# 3-9.net
KiCad netlist of a schematic drawn in Altium Designer
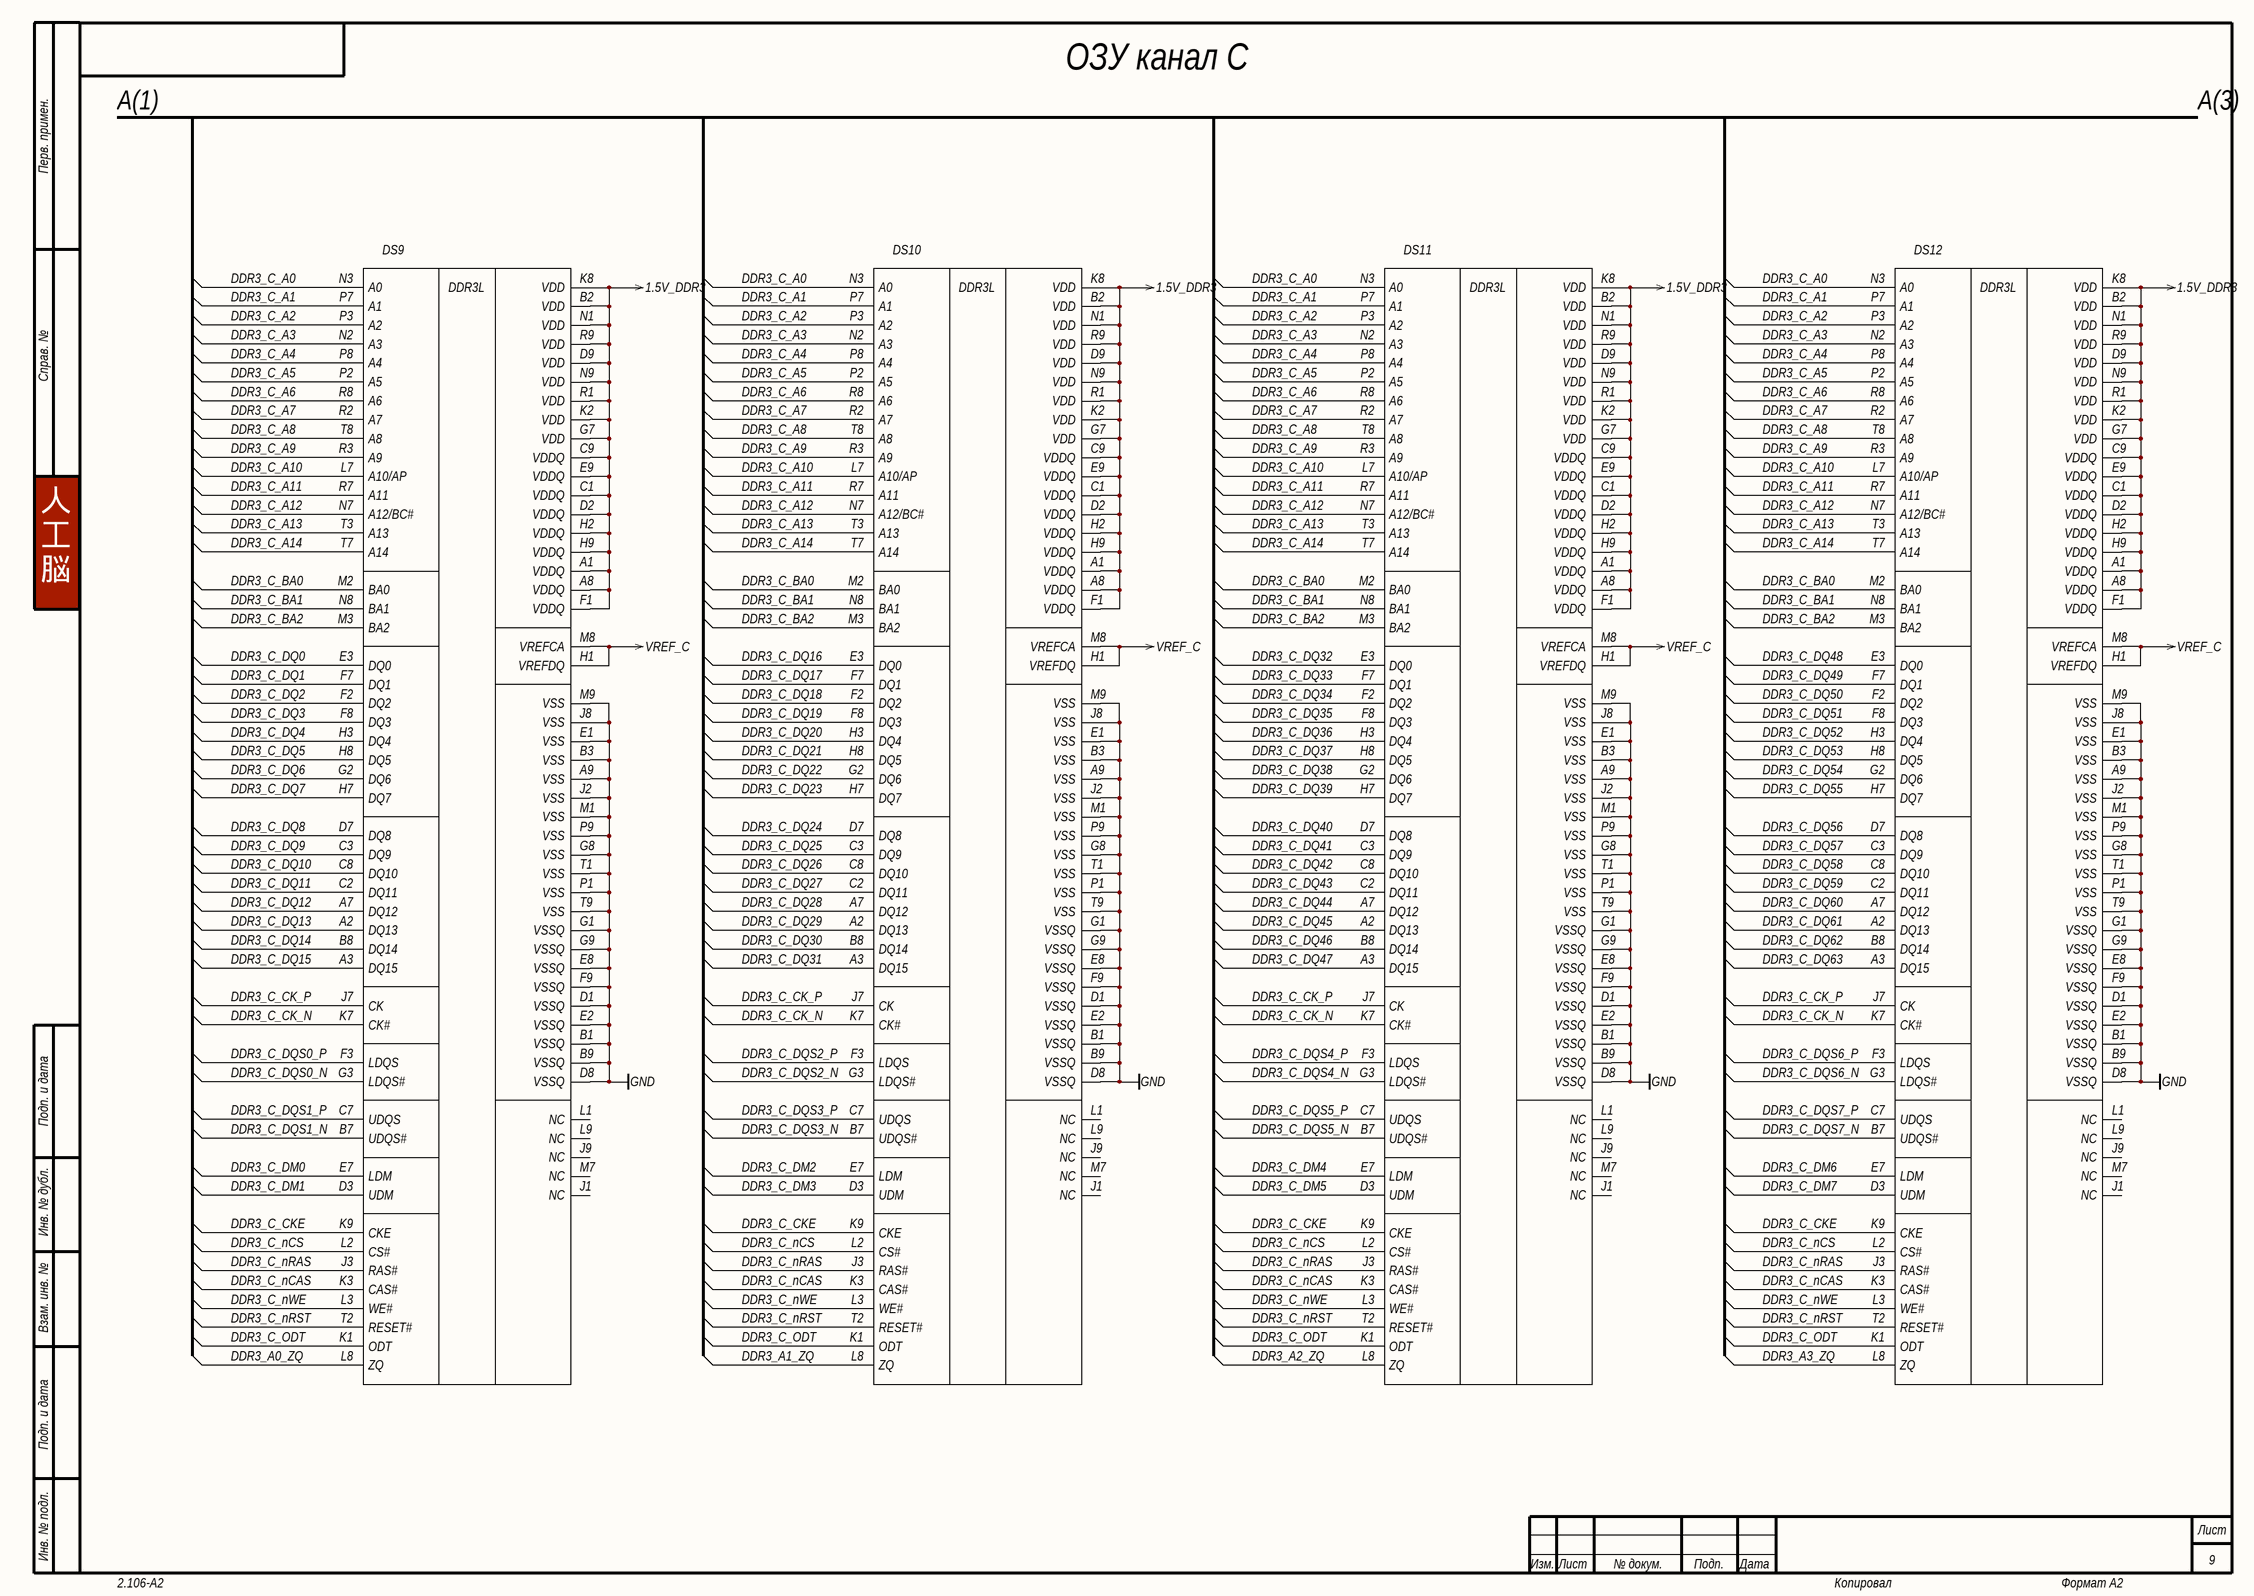
[diagram p0: Э3-9.SchDoc]

(export (version "E")
  (design (tool "Eeschema 10.0.6"))
  (components
    (comp (ref "DS9")
      (value "1")
      (footprint "96-FBGA")
      (description "32 Megx16x8 banks DDR3L SDRAM")
      (fields (field (name "MANUFACTURER") "Micron Technology, Inc."))
      (libsource (lib "Digital") (part "MT41K256M16TW-107IT{colon}P"))
    )
    (comp (ref "DS10")
      (value "1")
      (footprint "96-FBGA")
      (description "32 Megx16x8 banks DDR3L SDRAM")
      (fields (field (name "MANUFACTURER") "Micron Technology, Inc."))
      (libsource (lib "Digital") (part "MT41K256M16TW-107IT{colon}P"))
    )
    (comp (ref "DS11")
      (value "1")
      (footprint "96-FBGA")
      (description "32 Megx16x8 banks DDR3L SDRAM")
      (fields (field (name "MANUFACTURER") "Micron Technology, Inc."))
      (libsource (lib "Digital") (part "MT41K256M16TW-107IT{colon}P"))
    )
    (comp (ref "DS12")
      (value "1")
      (footprint "96-FBGA")
      (description "32 Megx16x8 banks DDR3L SDRAM")
      (fields (field (name "MANUFACTURER") "Micron Technology, Inc."))
      (libsource (lib "Digital") (part "MT41K256M16TW-107IT{colon}P"))
    )
  )
  (nets
    (net (code "1") (name "/DDR3_A0_ZQ") (class "Default")
      (node (ref "DS9") (pin "L8") (pinfunction "ZQ_L8") (pintype "passive"))
    )
    (net (code "2") (name "/DDR3_A1_ZQ") (class "Default")
      (node (ref "DS10") (pin "L8") (pinfunction "ZQ_L8") (pintype "passive"))
    )
    (net (code "3") (name "/DDR3_A2_ZQ") (class "Default")
      (node (ref "DS11") (pin "L8") (pinfunction "ZQ_L8") (pintype "passive"))
    )
    (net (code "4") (name "/DDR3_A3_ZQ") (class "Default")
      (node (ref "DS12") (pin "L8") (pinfunction "ZQ_L8") (pintype "passive"))
    )
    (net (code "5") (name "/DDR3_C_A0") (class "Default")
      (node (ref "DS10") (pin "N3") (pinfunction "A0_N3") (pintype "passive"))
      (node (ref "DS11") (pin "N3") (pinfunction "A0_N3") (pintype "passive"))
      (node (ref "DS12") (pin "N3") (pinfunction "A0_N3") (pintype "passive"))
      (node (ref "DS9") (pin "N3") (pinfunction "A0_N3") (pintype "passive"))
    )
    (net (code "6") (name "/DDR3_C_A1") (class "Default")
      (node (ref "DS10") (pin "P7") (pinfunction "A1_P7") (pintype "passive"))
      (node (ref "DS11") (pin "P7") (pinfunction "A1_P7") (pintype "passive"))
      (node (ref "DS12") (pin "P7") (pinfunction "A1_P7") (pintype "passive"))
      (node (ref "DS9") (pin "P7") (pinfunction "A1_P7") (pintype "passive"))
    )
    (net (code "7") (name "/DDR3_C_A2") (class "Default")
      (node (ref "DS10") (pin "P3") (pinfunction "A2_P3") (pintype "passive"))
      (node (ref "DS11") (pin "P3") (pinfunction "A2_P3") (pintype "passive"))
      (node (ref "DS12") (pin "P3") (pinfunction "A2_P3") (pintype "passive"))
      (node (ref "DS9") (pin "P3") (pinfunction "A2_P3") (pintype "passive"))
    )
    (net (code "8") (name "/DDR3_C_A3") (class "Default")
      (node (ref "DS10") (pin "N2") (pinfunction "A3_N2") (pintype "passive"))
      (node (ref "DS11") (pin "N2") (pinfunction "A3_N2") (pintype "passive"))
      (node (ref "DS12") (pin "N2") (pinfunction "A3_N2") (pintype "passive"))
      (node (ref "DS9") (pin "N2") (pinfunction "A3_N2") (pintype "passive"))
    )
    (net (code "9") (name "/DDR3_C_A4") (class "Default")
      (node (ref "DS10") (pin "P8") (pinfunction "A4_P8") (pintype "passive"))
      (node (ref "DS11") (pin "P8") (pinfunction "A4_P8") (pintype "passive"))
      (node (ref "DS12") (pin "P8") (pinfunction "A4_P8") (pintype "passive"))
      (node (ref "DS9") (pin "P8") (pinfunction "A4_P8") (pintype "passive"))
    )
    (net (code "10") (name "/DDR3_C_A5") (class "Default")
      (node (ref "DS10") (pin "P2") (pinfunction "A5_P2") (pintype "passive"))
      (node (ref "DS11") (pin "P2") (pinfunction "A5_P2") (pintype "passive"))
      (node (ref "DS12") (pin "P2") (pinfunction "A5_P2") (pintype "passive"))
      (node (ref "DS9") (pin "P2") (pinfunction "A5_P2") (pintype "passive"))
    )
    (net (code "11") (name "/DDR3_C_A6") (class "Default")
      (node (ref "DS10") (pin "R8") (pinfunction "A6_R8") (pintype "passive"))
      (node (ref "DS11") (pin "R8") (pinfunction "A6_R8") (pintype "passive"))
      (node (ref "DS12") (pin "R8") (pinfunction "A6_R8") (pintype "passive"))
      (node (ref "DS9") (pin "R8") (pinfunction "A6_R8") (pintype "passive"))
    )
    (net (code "12") (name "/DDR3_C_A7") (class "Default")
      (node (ref "DS10") (pin "R2") (pinfunction "A7_R2") (pintype "passive"))
      (node (ref "DS11") (pin "R2") (pinfunction "A7_R2") (pintype "passive"))
      (node (ref "DS12") (pin "R2") (pinfunction "A7_R2") (pintype "passive"))
      (node (ref "DS9") (pin "R2") (pinfunction "A7_R2") (pintype "passive"))
    )
    (net (code "13") (name "/DDR3_C_A8") (class "Default")
      (node (ref "DS10") (pin "T8") (pinfunction "A8_T8") (pintype "passive"))
      (node (ref "DS11") (pin "T8") (pinfunction "A8_T8") (pintype "passive"))
      (node (ref "DS12") (pin "T8") (pinfunction "A8_T8") (pintype "passive"))
      (node (ref "DS9") (pin "T8") (pinfunction "A8_T8") (pintype "passive"))
    )
    (net (code "14") (name "/DDR3_C_A9") (class "Default")
      (node (ref "DS10") (pin "R3") (pinfunction "A9_R3") (pintype "passive"))
      (node (ref "DS11") (pin "R3") (pinfunction "A9_R3") (pintype "passive"))
      (node (ref "DS12") (pin "R3") (pinfunction "A9_R3") (pintype "passive"))
      (node (ref "DS9") (pin "R3") (pinfunction "A9_R3") (pintype "passive"))
    )
    (net (code "15") (name "/DDR3_C_A10") (class "Default")
      (node (ref "DS10") (pin "L7") (pinfunction "A10/AP_L7") (pintype "passive"))
      (node (ref "DS11") (pin "L7") (pinfunction "A10/AP_L7") (pintype "passive"))
      (node (ref "DS12") (pin "L7") (pinfunction "A10/AP_L7") (pintype "passive"))
      (node (ref "DS9") (pin "L7") (pinfunction "A10/AP_L7") (pintype "passive"))
    )
    (net (code "16") (name "/DDR3_C_A11") (class "Default")
      (node (ref "DS10") (pin "R7") (pinfunction "A11_R7") (pintype "passive"))
      (node (ref "DS11") (pin "R7") (pinfunction "A11_R7") (pintype "passive"))
      (node (ref "DS12") (pin "R7") (pinfunction "A11_R7") (pintype "passive"))
      (node (ref "DS9") (pin "R7") (pinfunction "A11_R7") (pintype "passive"))
    )
    (net (code "17") (name "/DDR3_C_A12") (class "Default")
      (node (ref "DS10") (pin "N7") (pinfunction "A12/BC#_N7") (pintype "passive"))
      (node (ref "DS11") (pin "N7") (pinfunction "A12/BC#_N7") (pintype "passive"))
      (node (ref "DS12") (pin "N7") (pinfunction "A12/BC#_N7") (pintype "passive"))
      (node (ref "DS9") (pin "N7") (pinfunction "A12/BC#_N7") (pintype "passive"))
    )
    (net (code "18") (name "/DDR3_C_A13") (class "Default")
      (node (ref "DS10") (pin "T3") (pinfunction "A13_T3") (pintype "passive"))
      (node (ref "DS11") (pin "T3") (pinfunction "A13_T3") (pintype "passive"))
      (node (ref "DS12") (pin "T3") (pinfunction "A13_T3") (pintype "passive"))
      (node (ref "DS9") (pin "T3") (pinfunction "A13_T3") (pintype "passive"))
    )
    (net (code "19") (name "/DDR3_C_A14") (class "Default")
      (node (ref "DS10") (pin "T7") (pinfunction "A14_T7") (pintype "passive"))
      (node (ref "DS11") (pin "T7") (pinfunction "A14_T7") (pintype "passive"))
      (node (ref "DS12") (pin "T7") (pinfunction "A14_T7") (pintype "passive"))
      (node (ref "DS9") (pin "T7") (pinfunction "A14_T7") (pintype "passive"))
    )
    (net (code "20") (name "/DDR3_C_BA0") (class "Default")
      (node (ref "DS10") (pin "M2") (pinfunction "BA0_M2") (pintype "passive"))
      (node (ref "DS11") (pin "M2") (pinfunction "BA0_M2") (pintype "passive"))
      (node (ref "DS12") (pin "M2") (pinfunction "BA0_M2") (pintype "passive"))
      (node (ref "DS9") (pin "M2") (pinfunction "BA0_M2") (pintype "passive"))
    )
    (net (code "21") (name "/DDR3_C_BA1") (class "Default")
      (node (ref "DS10") (pin "N8") (pinfunction "BA1_N8") (pintype "passive"))
      (node (ref "DS11") (pin "N8") (pinfunction "BA1_N8") (pintype "passive"))
      (node (ref "DS12") (pin "N8") (pinfunction "BA1_N8") (pintype "passive"))
      (node (ref "DS9") (pin "N8") (pinfunction "BA1_N8") (pintype "passive"))
    )
    (net (code "22") (name "/DDR3_C_BA2") (class "Default")
      (node (ref "DS10") (pin "M3") (pinfunction "BA2_M3") (pintype "passive"))
      (node (ref "DS11") (pin "M3") (pinfunction "BA2_M3") (pintype "passive"))
      (node (ref "DS12") (pin "M3") (pinfunction "BA2_M3") (pintype "passive"))
      (node (ref "DS9") (pin "M3") (pinfunction "BA2_M3") (pintype "passive"))
    )
    (net (code "23") (name "/DDR3_C_CKE") (class "Default")
      (node (ref "DS10") (pin "K9") (pinfunction "CKE_K9") (pintype "passive"))
      (node (ref "DS11") (pin "K9") (pinfunction "CKE_K9") (pintype "passive"))
      (node (ref "DS12") (pin "K9") (pinfunction "CKE_K9") (pintype "passive"))
      (node (ref "DS9") (pin "K9") (pinfunction "CKE_K9") (pintype "passive"))
    )
    (net (code "24") (name "/DDR3_C_CK_N") (class "Default")
      (node (ref "DS10") (pin "K7") (pinfunction "CK#_K7") (pintype "passive"))
      (node (ref "DS11") (pin "K7") (pinfunction "CK#_K7") (pintype "passive"))
      (node (ref "DS12") (pin "K7") (pinfunction "CK#_K7") (pintype "passive"))
      (node (ref "DS9") (pin "K7") (pinfunction "CK#_K7") (pintype "passive"))
    )
    (net (code "25") (name "/DDR3_C_CK_P") (class "Default")
      (node (ref "DS10") (pin "J7") (pinfunction "CK_J7") (pintype "passive"))
      (node (ref "DS11") (pin "J7") (pinfunction "CK_J7") (pintype "passive"))
      (node (ref "DS12") (pin "J7") (pinfunction "CK_J7") (pintype "passive"))
      (node (ref "DS9") (pin "J7") (pinfunction "CK_J7") (pintype "passive"))
    )
    (net (code "26") (name "/DDR3_C_DM0") (class "Default")
      (node (ref "DS9") (pin "E7") (pinfunction "LDM_E7") (pintype "passive"))
    )
    (net (code "27") (name "/DDR3_C_DM1") (class "Default")
      (node (ref "DS9") (pin "D3") (pinfunction "UDM_D3") (pintype "passive"))
    )
    (net (code "28") (name "/DDR3_C_DM2") (class "Default")
      (node (ref "DS10") (pin "E7") (pinfunction "LDM_E7") (pintype "passive"))
    )
    (net (code "29") (name "/DDR3_C_DM3") (class "Default")
      (node (ref "DS10") (pin "D3") (pinfunction "UDM_D3") (pintype "passive"))
    )
    (net (code "30") (name "/DDR3_C_DM4") (class "Default")
      (node (ref "DS11") (pin "E7") (pinfunction "LDM_E7") (pintype "passive"))
    )
    (net (code "31") (name "/DDR3_C_DM5") (class "Default")
      (node (ref "DS11") (pin "D3") (pinfunction "UDM_D3") (pintype "passive"))
    )
    (net (code "32") (name "/DDR3_C_DM6") (class "Default")
      (node (ref "DS12") (pin "E7") (pinfunction "LDM_E7") (pintype "passive"))
    )
    (net (code "33") (name "/DDR3_C_DM7") (class "Default")
      (node (ref "DS12") (pin "D3") (pinfunction "UDM_D3") (pintype "passive"))
    )
    (net (code "34") (name "/DDR3_C_DQ0") (class "Default")
      (node (ref "DS9") (pin "E3") (pinfunction "DQ0_E3") (pintype "passive"))
    )
    (net (code "35") (name "/DDR3_C_DQ1") (class "Default")
      (node (ref "DS9") (pin "F7") (pinfunction "DQ1_F7") (pintype "passive"))
    )
    (net (code "36") (name "/DDR3_C_DQ2") (class "Default")
      (node (ref "DS9") (pin "F2") (pinfunction "DQ2_F2") (pintype "passive"))
    )
    (net (code "37") (name "/DDR3_C_DQ3") (class "Default")
      (node (ref "DS9") (pin "F8") (pinfunction "DQ3_F8") (pintype "passive"))
    )
    (net (code "38") (name "/DDR3_C_DQ4") (class "Default")
      (node (ref "DS9") (pin "H3") (pinfunction "DQ4_H3") (pintype "passive"))
    )
    (net (code "39") (name "/DDR3_C_DQ5") (class "Default")
      (node (ref "DS9") (pin "H8") (pinfunction "DQ5_H8") (pintype "passive"))
    )
    (net (code "40") (name "/DDR3_C_DQ6") (class "Default")
      (node (ref "DS9") (pin "G2") (pinfunction "DQ6_G2") (pintype "passive"))
    )
    (net (code "41") (name "/DDR3_C_DQ7") (class "Default")
      (node (ref "DS9") (pin "H7") (pinfunction "DQ7_H7") (pintype "passive"))
    )
    (net (code "42") (name "/DDR3_C_DQ8") (class "Default")
      (node (ref "DS9") (pin "D7") (pinfunction "DQ8_D7") (pintype "passive"))
    )
    (net (code "43") (name "/DDR3_C_DQ9") (class "Default")
      (node (ref "DS9") (pin "C3") (pinfunction "DQ9_C3") (pintype "passive"))
    )
    (net (code "44") (name "/DDR3_C_DQ10") (class "Default")
      (node (ref "DS9") (pin "C8") (pinfunction "DQ10_C8") (pintype "passive"))
    )
    (net (code "45") (name "/DDR3_C_DQ11") (class "Default")
      (node (ref "DS9") (pin "C2") (pinfunction "DQ11_C2") (pintype "passive"))
    )
    (net (code "46") (name "/DDR3_C_DQ12") (class "Default")
      (node (ref "DS9") (pin "A7") (pinfunction "DQ12_A7") (pintype "passive"))
    )
    (net (code "47") (name "/DDR3_C_DQ13") (class "Default")
      (node (ref "DS9") (pin "A2") (pinfunction "DQ13_A2") (pintype "passive"))
    )
    (net (code "48") (name "/DDR3_C_DQ14") (class "Default")
      (node (ref "DS9") (pin "B8") (pinfunction "DQ14_B8") (pintype "passive"))
    )
    (net (code "49") (name "/DDR3_C_DQ15") (class "Default")
      (node (ref "DS9") (pin "A3") (pinfunction "DQ15_A3") (pintype "passive"))
    )
    (net (code "50") (name "/DDR3_C_DQ16") (class "Default")
      (node (ref "DS10") (pin "E3") (pinfunction "DQ0_E3") (pintype "passive"))
    )
    (net (code "51") (name "/DDR3_C_DQ17") (class "Default")
      (node (ref "DS10") (pin "F7") (pinfunction "DQ1_F7") (pintype "passive"))
    )
    (net (code "52") (name "/DDR3_C_DQ18") (class "Default")
      (node (ref "DS10") (pin "F2") (pinfunction "DQ2_F2") (pintype "passive"))
    )
    (net (code "53") (name "/DDR3_C_DQ19") (class "Default")
      (node (ref "DS10") (pin "F8") (pinfunction "DQ3_F8") (pintype "passive"))
    )
    (net (code "54") (name "/DDR3_C_DQ20") (class "Default")
      (node (ref "DS10") (pin "H3") (pinfunction "DQ4_H3") (pintype "passive"))
    )
    (net (code "55") (name "/DDR3_C_DQ21") (class "Default")
      (node (ref "DS10") (pin "H8") (pinfunction "DQ5_H8") (pintype "passive"))
    )
    (net (code "56") (name "/DDR3_C_DQ22") (class "Default")
      (node (ref "DS10") (pin "G2") (pinfunction "DQ6_G2") (pintype "passive"))
    )
    (net (code "57") (name "/DDR3_C_DQ23") (class "Default")
      (node (ref "DS10") (pin "H7") (pinfunction "DQ7_H7") (pintype "passive"))
    )
    (net (code "58") (name "/DDR3_C_DQ24") (class "Default")
      (node (ref "DS10") (pin "D7") (pinfunction "DQ8_D7") (pintype "passive"))
    )
    (net (code "59") (name "/DDR3_C_DQ25") (class "Default")
      (node (ref "DS10") (pin "C3") (pinfunction "DQ9_C3") (pintype "passive"))
    )
    (net (code "60") (name "/DDR3_C_DQ26") (class "Default")
      (node (ref "DS10") (pin "C8") (pinfunction "DQ10_C8") (pintype "passive"))
    )
    (net (code "61") (name "/DDR3_C_DQ27") (class "Default")
      (node (ref "DS10") (pin "C2") (pinfunction "DQ11_C2") (pintype "passive"))
    )
    (net (code "62") (name "/DDR3_C_DQ28") (class "Default")
      (node (ref "DS10") (pin "A7") (pinfunction "DQ12_A7") (pintype "passive"))
    )
    (net (code "63") (name "/DDR3_C_DQ29") (class "Default")
      (node (ref "DS10") (pin "A2") (pinfunction "DQ13_A2") (pintype "passive"))
    )
    (net (code "64") (name "/DDR3_C_DQ30") (class "Default")
      (node (ref "DS10") (pin "B8") (pinfunction "DQ14_B8") (pintype "passive"))
    )
    (net (code "65") (name "/DDR3_C_DQ31") (class "Default")
      (node (ref "DS10") (pin "A3") (pinfunction "DQ15_A3") (pintype "passive"))
    )
    (net (code "66") (name "/DDR3_C_DQ32") (class "Default")
      (node (ref "DS11") (pin "E3") (pinfunction "DQ0_E3") (pintype "passive"))
    )
    (net (code "67") (name "/DDR3_C_DQ33") (class "Default")
      (node (ref "DS11") (pin "F7") (pinfunction "DQ1_F7") (pintype "passive"))
    )
    (net (code "68") (name "/DDR3_C_DQ34") (class "Default")
      (node (ref "DS11") (pin "F2") (pinfunction "DQ2_F2") (pintype "passive"))
    )
    (net (code "69") (name "/DDR3_C_DQ35") (class "Default")
      (node (ref "DS11") (pin "F8") (pinfunction "DQ3_F8") (pintype "passive"))
    )
    (net (code "70") (name "/DDR3_C_DQ36") (class "Default")
      (node (ref "DS11") (pin "H3") (pinfunction "DQ4_H3") (pintype "passive"))
    )
    (net (code "71") (name "/DDR3_C_DQ37") (class "Default")
      (node (ref "DS11") (pin "H8") (pinfunction "DQ5_H8") (pintype "passive"))
    )
    (net (code "72") (name "/DDR3_C_DQ38") (class "Default")
      (node (ref "DS11") (pin "G2") (pinfunction "DQ6_G2") (pintype "passive"))
    )
    (net (code "73") (name "/DDR3_C_DQ39") (class "Default")
      (node (ref "DS11") (pin "H7") (pinfunction "DQ7_H7") (pintype "passive"))
    )
    (net (code "74") (name "/DDR3_C_DQ40") (class "Default")
      (node (ref "DS11") (pin "D7") (pinfunction "DQ8_D7") (pintype "passive"))
    )
    (net (code "75") (name "/DDR3_C_DQ41") (class "Default")
      (node (ref "DS11") (pin "C3") (pinfunction "DQ9_C3") (pintype "passive"))
    )
    (net (code "76") (name "/DDR3_C_DQ42") (class "Default")
      (node (ref "DS11") (pin "C8") (pinfunction "DQ10_C8") (pintype "passive"))
    )
    (net (code "77") (name "/DDR3_C_DQ43") (class "Default")
      (node (ref "DS11") (pin "C2") (pinfunction "DQ11_C2") (pintype "passive"))
    )
    (net (code "78") (name "/DDR3_C_DQ44") (class "Default")
      (node (ref "DS11") (pin "A7") (pinfunction "DQ12_A7") (pintype "passive"))
    )
    (net (code "79") (name "/DDR3_C_DQ45") (class "Default")
      (node (ref "DS11") (pin "A2") (pinfunction "DQ13_A2") (pintype "passive"))
    )
    (net (code "80") (name "/DDR3_C_DQ46") (class "Default")
      (node (ref "DS11") (pin "B8") (pinfunction "DQ14_B8") (pintype "passive"))
    )
    (net (code "81") (name "/DDR3_C_DQ47") (class "Default")
      (node (ref "DS11") (pin "A3") (pinfunction "DQ15_A3") (pintype "passive"))
    )
    (net (code "82") (name "/DDR3_C_DQ48") (class "Default")
      (node (ref "DS12") (pin "E3") (pinfunction "DQ0_E3") (pintype "passive"))
    )
    (net (code "83") (name "/DDR3_C_DQ49") (class "Default")
      (node (ref "DS12") (pin "F7") (pinfunction "DQ1_F7") (pintype "passive"))
    )
    (net (code "84") (name "/DDR3_C_DQ50") (class "Default")
      (node (ref "DS12") (pin "F2") (pinfunction "DQ2_F2") (pintype "passive"))
    )
    (net (code "85") (name "/DDR3_C_DQ51") (class "Default")
      (node (ref "DS12") (pin "F8") (pinfunction "DQ3_F8") (pintype "passive"))
    )
    (net (code "86") (name "/DDR3_C_DQ52") (class "Default")
      (node (ref "DS12") (pin "H3") (pinfunction "DQ4_H3") (pintype "passive"))
    )
    (net (code "87") (name "/DDR3_C_DQ53") (class "Default")
      (node (ref "DS12") (pin "H8") (pinfunction "DQ5_H8") (pintype "passive"))
    )
    (net (code "88") (name "/DDR3_C_DQ54") (class "Default")
      (node (ref "DS12") (pin "G2") (pinfunction "DQ6_G2") (pintype "passive"))
    )
    (net (code "89") (name "/DDR3_C_DQ55") (class "Default")
      (node (ref "DS12") (pin "H7") (pinfunction "DQ7_H7") (pintype "passive"))
    )
    (net (code "90") (name "/DDR3_C_DQ56") (class "Default")
      (node (ref "DS12") (pin "D7") (pinfunction "DQ8_D7") (pintype "passive"))
    )
    (net (code "91") (name "/DDR3_C_DQ57") (class "Default")
      (node (ref "DS12") (pin "C3") (pinfunction "DQ9_C3") (pintype "passive"))
    )
    (net (code "92") (name "/DDR3_C_DQ58") (class "Default")
      (node (ref "DS12") (pin "C8") (pinfunction "DQ10_C8") (pintype "passive"))
    )
    (net (code "93") (name "/DDR3_C_DQ59") (class "Default")
      (node (ref "DS12") (pin "C2") (pinfunction "DQ11_C2") (pintype "passive"))
    )
    (net (code "94") (name "/DDR3_C_DQ60") (class "Default")
      (node (ref "DS12") (pin "A7") (pinfunction "DQ12_A7") (pintype "passive"))
    )
    (net (code "95") (name "/DDR3_C_DQ61") (class "Default")
      (node (ref "DS12") (pin "A2") (pinfunction "DQ13_A2") (pintype "passive"))
    )
    (net (code "96") (name "/DDR3_C_DQ62") (class "Default")
      (node (ref "DS12") (pin "B8") (pinfunction "DQ14_B8") (pintype "passive"))
    )
    (net (code "97") (name "/DDR3_C_DQ63") (class "Default")
      (node (ref "DS12") (pin "A3") (pinfunction "DQ15_A3") (pintype "passive"))
    )
    (net (code "98") (name "/DDR3_C_DQS0_N") (class "Default")
      (node (ref "DS9") (pin "G3") (pinfunction "LDQS#_G3") (pintype "passive"))
    )
    (net (code "99") (name "/DDR3_C_DQS0_P") (class "Default")
      (node (ref "DS9") (pin "F3") (pinfunction "LDQS_F3") (pintype "passive"))
    )
    (net (code "100") (name "/DDR3_C_DQS1_N") (class "Default")
      (node (ref "DS9") (pin "B7") (pinfunction "UDQS#_B7") (pintype "passive"))
    )
    (net (code "101") (name "/DDR3_C_DQS1_P") (class "Default")
      (node (ref "DS9") (pin "C7") (pinfunction "UDQS_C7") (pintype "passive"))
    )
    (net (code "102") (name "/DDR3_C_DQS2_N") (class "Default")
      (node (ref "DS10") (pin "G3") (pinfunction "LDQS#_G3") (pintype "passive"))
    )
    (net (code "103") (name "/DDR3_C_DQS2_P") (class "Default")
      (node (ref "DS10") (pin "F3") (pinfunction "LDQS_F3") (pintype "passive"))
    )
    (net (code "104") (name "/DDR3_C_DQS3_N") (class "Default")
      (node (ref "DS10") (pin "B7") (pinfunction "UDQS#_B7") (pintype "passive"))
    )
    (net (code "105") (name "/DDR3_C_DQS3_P") (class "Default")
      (node (ref "DS10") (pin "C7") (pinfunction "UDQS_C7") (pintype "passive"))
    )
    (net (code "106") (name "/DDR3_C_DQS4_N") (class "Default")
      (node (ref "DS11") (pin "G3") (pinfunction "LDQS#_G3") (pintype "passive"))
    )
    (net (code "107") (name "/DDR3_C_DQS4_P") (class "Default")
      (node (ref "DS11") (pin "F3") (pinfunction "LDQS_F3") (pintype "passive"))
    )
    (net (code "108") (name "/DDR3_C_DQS5_N") (class "Default")
      (node (ref "DS11") (pin "B7") (pinfunction "UDQS#_B7") (pintype "passive"))
    )
    (net (code "109") (name "/DDR3_C_DQS5_P") (class "Default")
      (node (ref "DS11") (pin "C7") (pinfunction "UDQS_C7") (pintype "passive"))
    )
    (net (code "110") (name "/DDR3_C_DQS6_N") (class "Default")
      (node (ref "DS12") (pin "G3") (pinfunction "LDQS#_G3") (pintype "passive"))
    )
    (net (code "111") (name "/DDR3_C_DQS6_P") (class "Default")
      (node (ref "DS12") (pin "F3") (pinfunction "LDQS_F3") (pintype "passive"))
    )
    (net (code "112") (name "/DDR3_C_DQS7_N") (class "Default")
      (node (ref "DS12") (pin "B7") (pinfunction "UDQS#_B7") (pintype "passive"))
    )
    (net (code "113") (name "/DDR3_C_DQS7_P") (class "Default")
      (node (ref "DS12") (pin "C7") (pinfunction "UDQS_C7") (pintype "passive"))
    )
    (net (code "114") (name "/DDR3_C_ODT") (class "Default")
      (node (ref "DS10") (pin "K1") (pinfunction "ODT_K1") (pintype "passive"))
      (node (ref "DS11") (pin "K1") (pinfunction "ODT_K1") (pintype "passive"))
      (node (ref "DS12") (pin "K1") (pinfunction "ODT_K1") (pintype "passive"))
      (node (ref "DS9") (pin "K1") (pinfunction "ODT_K1") (pintype "passive"))
    )
    (net (code "115") (name "/DDR3_C_nCAS") (class "Default")
      (node (ref "DS10") (pin "K3") (pinfunction "CAS#_K3") (pintype "passive"))
      (node (ref "DS11") (pin "K3") (pinfunction "CAS#_K3") (pintype "passive"))
      (node (ref "DS12") (pin "K3") (pinfunction "CAS#_K3") (pintype "passive"))
      (node (ref "DS9") (pin "K3") (pinfunction "CAS#_K3") (pintype "passive"))
    )
    (net (code "116") (name "/DDR3_C_nCS") (class "Default")
      (node (ref "DS10") (pin "L2") (pinfunction "CS#_L2") (pintype "passive"))
      (node (ref "DS11") (pin "L2") (pinfunction "CS#_L2") (pintype "passive"))
      (node (ref "DS12") (pin "L2") (pinfunction "CS#_L2") (pintype "passive"))
      (node (ref "DS9") (pin "L2") (pinfunction "CS#_L2") (pintype "passive"))
    )
    (net (code "117") (name "/DDR3_C_nRAS") (class "Default")
      (node (ref "DS10") (pin "J3") (pinfunction "RAS#_J3") (pintype "passive"))
      (node (ref "DS11") (pin "J3") (pinfunction "RAS#_J3") (pintype "passive"))
      (node (ref "DS12") (pin "J3") (pinfunction "RAS#_J3") (pintype "passive"))
      (node (ref "DS9") (pin "J3") (pinfunction "RAS#_J3") (pintype "passive"))
    )
    (net (code "118") (name "/DDR3_C_nRST") (class "Default")
      (node (ref "DS10") (pin "T2") (pinfunction "RESET#_T2") (pintype "passive"))
      (node (ref "DS11") (pin "T2") (pinfunction "RESET#_T2") (pintype "passive"))
      (node (ref "DS12") (pin "T2") (pinfunction "RESET#_T2") (pintype "passive"))
      (node (ref "DS9") (pin "T2") (pinfunction "RESET#_T2") (pintype "passive"))
    )
    (net (code "119") (name "/DDR3_C_nWE") (class "Default")
      (node (ref "DS10") (pin "L3") (pinfunction "WE#_L3") (pintype "passive"))
      (node (ref "DS11") (pin "L3") (pinfunction "WE#_L3") (pintype "passive"))
      (node (ref "DS12") (pin "L3") (pinfunction "WE#_L3") (pintype "passive"))
      (node (ref "DS9") (pin "L3") (pinfunction "WE#_L3") (pintype "passive"))
    )
    (net (code "120") (name "1.5V_DDR3") (class "Default")
      (node (ref "DS10") (pin "A1") (pinfunction "VDDQ_A1") (pintype "passive"))
      (node (ref "DS10") (pin "A8") (pinfunction "VDDQ_A8") (pintype "passive"))
      (node (ref "DS10") (pin "B2") (pinfunction "VDD_B2") (pintype "passive"))
      (node (ref "DS10") (pin "C1") (pinfunction "VDDQ_C1") (pintype "passive"))
      (node (ref "DS10") (pin "C9") (pinfunction "VDDQ_C9") (pintype "passive"))
      (node (ref "DS10") (pin "D2") (pinfunction "VDDQ_D2") (pintype "passive"))
      (node (ref "DS10") (pin "D9") (pinfunction "VDD_D9") (pintype "passive"))
      (node (ref "DS10") (pin "E9") (pinfunction "VDDQ_E9") (pintype "passive"))
      (node (ref "DS10") (pin "F1") (pinfunction "VDDQ_F1") (pintype "passive"))
      (node (ref "DS10") (pin "G7") (pinfunction "VDD_G7") (pintype "passive"))
      (node (ref "DS10") (pin "H2") (pinfunction "VDDQ_H2") (pintype "passive"))
      (node (ref "DS10") (pin "H9") (pinfunction "VDDQ_H9") (pintype "passive"))
      (node (ref "DS10") (pin "K2") (pinfunction "VDD_K2") (pintype "passive"))
      (node (ref "DS10") (pin "K8") (pinfunction "VDD_K8") (pintype "passive"))
      (node (ref "DS10") (pin "N1") (pinfunction "VDD_N1") (pintype "passive"))
      (node (ref "DS10") (pin "N9") (pinfunction "VDD_N9") (pintype "passive"))
      (node (ref "DS10") (pin "R1") (pinfunction "VDD_R1") (pintype "passive"))
      (node (ref "DS10") (pin "R9") (pinfunction "VDD_R9") (pintype "passive"))
      (node (ref "DS11") (pin "A1") (pinfunction "VDDQ_A1") (pintype "passive"))
      (node (ref "DS11") (pin "A8") (pinfunction "VDDQ_A8") (pintype "passive"))
      (node (ref "DS11") (pin "B2") (pinfunction "VDD_B2") (pintype "passive"))
      (node (ref "DS11") (pin "C1") (pinfunction "VDDQ_C1") (pintype "passive"))
      (node (ref "DS11") (pin "C9") (pinfunction "VDDQ_C9") (pintype "passive"))
      (node (ref "DS11") (pin "D2") (pinfunction "VDDQ_D2") (pintype "passive"))
      (node (ref "DS11") (pin "D9") (pinfunction "VDD_D9") (pintype "passive"))
      (node (ref "DS11") (pin "E9") (pinfunction "VDDQ_E9") (pintype "passive"))
      (node (ref "DS11") (pin "F1") (pinfunction "VDDQ_F1") (pintype "passive"))
      (node (ref "DS11") (pin "G7") (pinfunction "VDD_G7") (pintype "passive"))
      (node (ref "DS11") (pin "H2") (pinfunction "VDDQ_H2") (pintype "passive"))
      (node (ref "DS11") (pin "H9") (pinfunction "VDDQ_H9") (pintype "passive"))
      (node (ref "DS11") (pin "K2") (pinfunction "VDD_K2") (pintype "passive"))
      (node (ref "DS11") (pin "K8") (pinfunction "VDD_K8") (pintype "passive"))
      (node (ref "DS11") (pin "N1") (pinfunction "VDD_N1") (pintype "passive"))
      (node (ref "DS11") (pin "N9") (pinfunction "VDD_N9") (pintype "passive"))
      (node (ref "DS11") (pin "R1") (pinfunction "VDD_R1") (pintype "passive"))
      (node (ref "DS11") (pin "R9") (pinfunction "VDD_R9") (pintype "passive"))
      (node (ref "DS12") (pin "A1") (pinfunction "VDDQ_A1") (pintype "passive"))
      (node (ref "DS12") (pin "A8") (pinfunction "VDDQ_A8") (pintype "passive"))
      (node (ref "DS12") (pin "B2") (pinfunction "VDD_B2") (pintype "passive"))
      (node (ref "DS12") (pin "C1") (pinfunction "VDDQ_C1") (pintype "passive"))
      (node (ref "DS12") (pin "C9") (pinfunction "VDDQ_C9") (pintype "passive"))
      (node (ref "DS12") (pin "D2") (pinfunction "VDDQ_D2") (pintype "passive"))
      (node (ref "DS12") (pin "D9") (pinfunction "VDD_D9") (pintype "passive"))
      (node (ref "DS12") (pin "E9") (pinfunction "VDDQ_E9") (pintype "passive"))
      (node (ref "DS12") (pin "F1") (pinfunction "VDDQ_F1") (pintype "passive"))
      (node (ref "DS12") (pin "G7") (pinfunction "VDD_G7") (pintype "passive"))
      (node (ref "DS12") (pin "H2") (pinfunction "VDDQ_H2") (pintype "passive"))
      (node (ref "DS12") (pin "H9") (pinfunction "VDDQ_H9") (pintype "passive"))
      (node (ref "DS12") (pin "K2") (pinfunction "VDD_K2") (pintype "passive"))
      (node (ref "DS12") (pin "K8") (pinfunction "VDD_K8") (pintype "passive"))
      (node (ref "DS12") (pin "N1") (pinfunction "VDD_N1") (pintype "passive"))
      (node (ref "DS12") (pin "N9") (pinfunction "VDD_N9") (pintype "passive"))
      (node (ref "DS12") (pin "R1") (pinfunction "VDD_R1") (pintype "passive"))
      (node (ref "DS12") (pin "R9") (pinfunction "VDD_R9") (pintype "passive"))
      (node (ref "DS9") (pin "A1") (pinfunction "VDDQ_A1") (pintype "passive"))
      (node (ref "DS9") (pin "A8") (pinfunction "VDDQ_A8") (pintype "passive"))
      (node (ref "DS9") (pin "B2") (pinfunction "VDD_B2") (pintype "passive"))
      (node (ref "DS9") (pin "C1") (pinfunction "VDDQ_C1") (pintype "passive"))
      (node (ref "DS9") (pin "C9") (pinfunction "VDDQ_C9") (pintype "passive"))
      (node (ref "DS9") (pin "D2") (pinfunction "VDDQ_D2") (pintype "passive"))
      (node (ref "DS9") (pin "D9") (pinfunction "VDD_D9") (pintype "passive"))
      (node (ref "DS9") (pin "E9") (pinfunction "VDDQ_E9") (pintype "passive"))
      (node (ref "DS9") (pin "F1") (pinfunction "VDDQ_F1") (pintype "passive"))
      (node (ref "DS9") (pin "G7") (pinfunction "VDD_G7") (pintype "passive"))
      (node (ref "DS9") (pin "H2") (pinfunction "VDDQ_H2") (pintype "passive"))
      (node (ref "DS9") (pin "H9") (pinfunction "VDDQ_H9") (pintype "passive"))
      (node (ref "DS9") (pin "K2") (pinfunction "VDD_K2") (pintype "passive"))
      (node (ref "DS9") (pin "K8") (pinfunction "VDD_K8") (pintype "passive"))
      (node (ref "DS9") (pin "N1") (pinfunction "VDD_N1") (pintype "passive"))
      (node (ref "DS9") (pin "N9") (pinfunction "VDD_N9") (pintype "passive"))
      (node (ref "DS9") (pin "R1") (pinfunction "VDD_R1") (pintype "passive"))
      (node (ref "DS9") (pin "R9") (pinfunction "VDD_R9") (pintype "passive"))
    )
    (net (code "121") (name "GND") (class "Default")
      (node (ref "DS10") (pin "A9") (pinfunction "VSS_A9") (pintype "passive"))
      (node (ref "DS10") (pin "B1") (pinfunction "VSSQ_B1") (pintype "passive"))
      (node (ref "DS10") (pin "B3") (pinfunction "VSS_B3") (pintype "passive"))
      (node (ref "DS10") (pin "B9") (pinfunction "VSSQ_B9") (pintype "passive"))
      (node (ref "DS10") (pin "D1") (pinfunction "VSSQ_D1") (pintype "passive"))
      (node (ref "DS10") (pin "D8") (pinfunction "VSSQ_D8") (pintype "passive"))
      (node (ref "DS10") (pin "E1") (pinfunction "VSS_E1") (pintype "passive"))
      (node (ref "DS10") (pin "E2") (pinfunction "VSSQ_E2") (pintype "passive"))
      (node (ref "DS10") (pin "E8") (pinfunction "VSSQ_E8") (pintype "passive"))
      (node (ref "DS10") (pin "F9") (pinfunction "VSSQ_F9") (pintype "passive"))
      (node (ref "DS10") (pin "G1") (pinfunction "VSSQ_G1") (pintype "passive"))
      (node (ref "DS10") (pin "G8") (pinfunction "VSS_G8") (pintype "passive"))
      (node (ref "DS10") (pin "G9") (pinfunction "VSSQ_G9") (pintype "passive"))
      (node (ref "DS10") (pin "J2") (pinfunction "VSS_J2") (pintype "passive"))
      (node (ref "DS10") (pin "J8") (pinfunction "VSS_J8") (pintype "passive"))
      (node (ref "DS10") (pin "M1") (pinfunction "VSS_M1") (pintype "passive"))
      (node (ref "DS10") (pin "M9") (pinfunction "VSS_M9") (pintype "passive"))
      (node (ref "DS10") (pin "P1") (pinfunction "VSS_P1") (pintype "passive"))
      (node (ref "DS10") (pin "P9") (pinfunction "VSS_P9") (pintype "passive"))
      (node (ref "DS10") (pin "T1") (pinfunction "VSS_T1") (pintype "passive"))
      (node (ref "DS10") (pin "T9") (pinfunction "VSS_T9") (pintype "passive"))
      (node (ref "DS11") (pin "A9") (pinfunction "VSS_A9") (pintype "passive"))
      (node (ref "DS11") (pin "B1") (pinfunction "VSSQ_B1") (pintype "passive"))
      (node (ref "DS11") (pin "B3") (pinfunction "VSS_B3") (pintype "passive"))
      (node (ref "DS11") (pin "B9") (pinfunction "VSSQ_B9") (pintype "passive"))
      (node (ref "DS11") (pin "D1") (pinfunction "VSSQ_D1") (pintype "passive"))
      (node (ref "DS11") (pin "D8") (pinfunction "VSSQ_D8") (pintype "passive"))
      (node (ref "DS11") (pin "E1") (pinfunction "VSS_E1") (pintype "passive"))
      (node (ref "DS11") (pin "E2") (pinfunction "VSSQ_E2") (pintype "passive"))
      (node (ref "DS11") (pin "E8") (pinfunction "VSSQ_E8") (pintype "passive"))
      (node (ref "DS11") (pin "F9") (pinfunction "VSSQ_F9") (pintype "passive"))
      (node (ref "DS11") (pin "G1") (pinfunction "VSSQ_G1") (pintype "passive"))
      (node (ref "DS11") (pin "G8") (pinfunction "VSS_G8") (pintype "passive"))
      (node (ref "DS11") (pin "G9") (pinfunction "VSSQ_G9") (pintype "passive"))
      (node (ref "DS11") (pin "J2") (pinfunction "VSS_J2") (pintype "passive"))
      (node (ref "DS11") (pin "J8") (pinfunction "VSS_J8") (pintype "passive"))
      (node (ref "DS11") (pin "M1") (pinfunction "VSS_M1") (pintype "passive"))
      (node (ref "DS11") (pin "M9") (pinfunction "VSS_M9") (pintype "passive"))
      (node (ref "DS11") (pin "P1") (pinfunction "VSS_P1") (pintype "passive"))
      (node (ref "DS11") (pin "P9") (pinfunction "VSS_P9") (pintype "passive"))
      (node (ref "DS11") (pin "T1") (pinfunction "VSS_T1") (pintype "passive"))
      (node (ref "DS11") (pin "T9") (pinfunction "VSS_T9") (pintype "passive"))
      (node (ref "DS12") (pin "A9") (pinfunction "VSS_A9") (pintype "passive"))
      (node (ref "DS12") (pin "B1") (pinfunction "VSSQ_B1") (pintype "passive"))
      (node (ref "DS12") (pin "B3") (pinfunction "VSS_B3") (pintype "passive"))
      (node (ref "DS12") (pin "B9") (pinfunction "VSSQ_B9") (pintype "passive"))
      (node (ref "DS12") (pin "D1") (pinfunction "VSSQ_D1") (pintype "passive"))
      (node (ref "DS12") (pin "D8") (pinfunction "VSSQ_D8") (pintype "passive"))
      (node (ref "DS12") (pin "E1") (pinfunction "VSS_E1") (pintype "passive"))
      (node (ref "DS12") (pin "E2") (pinfunction "VSSQ_E2") (pintype "passive"))
      (node (ref "DS12") (pin "E8") (pinfunction "VSSQ_E8") (pintype "passive"))
      (node (ref "DS12") (pin "F9") (pinfunction "VSSQ_F9") (pintype "passive"))
      (node (ref "DS12") (pin "G1") (pinfunction "VSSQ_G1") (pintype "passive"))
      (node (ref "DS12") (pin "G8") (pinfunction "VSS_G8") (pintype "passive"))
      (node (ref "DS12") (pin "G9") (pinfunction "VSSQ_G9") (pintype "passive"))
      (node (ref "DS12") (pin "J2") (pinfunction "VSS_J2") (pintype "passive"))
      (node (ref "DS12") (pin "J8") (pinfunction "VSS_J8") (pintype "passive"))
      (node (ref "DS12") (pin "M1") (pinfunction "VSS_M1") (pintype "passive"))
      (node (ref "DS12") (pin "M9") (pinfunction "VSS_M9") (pintype "passive"))
      (node (ref "DS12") (pin "P1") (pinfunction "VSS_P1") (pintype "passive"))
      (node (ref "DS12") (pin "P9") (pinfunction "VSS_P9") (pintype "passive"))
      (node (ref "DS12") (pin "T1") (pinfunction "VSS_T1") (pintype "passive"))
      (node (ref "DS12") (pin "T9") (pinfunction "VSS_T9") (pintype "passive"))
      (node (ref "DS9") (pin "A9") (pinfunction "VSS_A9") (pintype "passive"))
      (node (ref "DS9") (pin "B1") (pinfunction "VSSQ_B1") (pintype "passive"))
      (node (ref "DS9") (pin "B3") (pinfunction "VSS_B3") (pintype "passive"))
      (node (ref "DS9") (pin "B9") (pinfunction "VSSQ_B9") (pintype "passive"))
      (node (ref "DS9") (pin "D1") (pinfunction "VSSQ_D1") (pintype "passive"))
      (node (ref "DS9") (pin "D8") (pinfunction "VSSQ_D8") (pintype "passive"))
      (node (ref "DS9") (pin "E1") (pinfunction "VSS_E1") (pintype "passive"))
      (node (ref "DS9") (pin "E2") (pinfunction "VSSQ_E2") (pintype "passive"))
      (node (ref "DS9") (pin "E8") (pinfunction "VSSQ_E8") (pintype "passive"))
      (node (ref "DS9") (pin "F9") (pinfunction "VSSQ_F9") (pintype "passive"))
      (node (ref "DS9") (pin "G1") (pinfunction "VSSQ_G1") (pintype "passive"))
      (node (ref "DS9") (pin "G8") (pinfunction "VSS_G8") (pintype "passive"))
      (node (ref "DS9") (pin "G9") (pinfunction "VSSQ_G9") (pintype "passive"))
      (node (ref "DS9") (pin "J2") (pinfunction "VSS_J2") (pintype "passive"))
      (node (ref "DS9") (pin "J8") (pinfunction "VSS_J8") (pintype "passive"))
      (node (ref "DS9") (pin "M1") (pinfunction "VSS_M1") (pintype "passive"))
      (node (ref "DS9") (pin "M9") (pinfunction "VSS_M9") (pintype "passive"))
      (node (ref "DS9") (pin "P1") (pinfunction "VSS_P1") (pintype "passive"))
      (node (ref "DS9") (pin "P9") (pinfunction "VSS_P9") (pintype "passive"))
      (node (ref "DS9") (pin "T1") (pinfunction "VSS_T1") (pintype "passive"))
      (node (ref "DS9") (pin "T9") (pinfunction "VSS_T9") (pintype "passive"))
    )
    (net (code "122") (name "VREF_C") (class "Default")
      (node (ref "DS10") (pin "H1") (pinfunction "VREFDQ_H1") (pintype "passive"))
      (node (ref "DS10") (pin "M8") (pinfunction "VREFCA_M8") (pintype "passive"))
      (node (ref "DS11") (pin "H1") (pinfunction "VREFDQ_H1") (pintype "passive"))
      (node (ref "DS11") (pin "M8") (pinfunction "VREFCA_M8") (pintype "passive"))
      (node (ref "DS12") (pin "H1") (pinfunction "VREFDQ_H1") (pintype "passive"))
      (node (ref "DS12") (pin "M8") (pinfunction "VREFCA_M8") (pintype "passive"))
      (node (ref "DS9") (pin "H1") (pinfunction "VREFDQ_H1") (pintype "passive"))
      (node (ref "DS9") (pin "M8") (pinfunction "VREFCA_M8") (pintype "passive"))
    )
    (net (code "123") (name "unconnected-(DS9-NC-PadJ1)") (class "Default")
      (node (ref "DS9") (pin "J1") (pinfunction "NC_J1") (pintype "passive"))
    )
    (net (code "124") (name "unconnected-(DS9-NC-PadJ9)") (class "Default")
      (node (ref "DS9") (pin "J9") (pinfunction "NC_J9") (pintype "passive"))
    )
    (net (code "125") (name "unconnected-(DS9-NC-PadL1)") (class "Default")
      (node (ref "DS9") (pin "L1") (pinfunction "NC_L1") (pintype "passive"))
    )
    (net (code "126") (name "unconnected-(DS9-NC-PadL9)") (class "Default")
      (node (ref "DS9") (pin "L9") (pinfunction "NC_L9") (pintype "passive"))
    )
    (net (code "127") (name "unconnected-(DS9-NC-PadM7)") (class "Default")
      (node (ref "DS9") (pin "M7") (pinfunction "NC_M7") (pintype "passive"))
    )
    (net (code "128") (name "unconnected-(DS10-NC-PadJ1)") (class "Default")
      (node (ref "DS10") (pin "J1") (pinfunction "NC_J1") (pintype "passive"))
    )
    (net (code "129") (name "unconnected-(DS10-NC-PadJ9)") (class "Default")
      (node (ref "DS10") (pin "J9") (pinfunction "NC_J9") (pintype "passive"))
    )
    (net (code "130") (name "unconnected-(DS10-NC-PadL1)") (class "Default")
      (node (ref "DS10") (pin "L1") (pinfunction "NC_L1") (pintype "passive"))
    )
    (net (code "131") (name "unconnected-(DS10-NC-PadL9)") (class "Default")
      (node (ref "DS10") (pin "L9") (pinfunction "NC_L9") (pintype "passive"))
    )
    (net (code "132") (name "unconnected-(DS10-NC-PadM7)") (class "Default")
      (node (ref "DS10") (pin "M7") (pinfunction "NC_M7") (pintype "passive"))
    )
    (net (code "133") (name "unconnected-(DS11-NC-PadJ1)") (class "Default")
      (node (ref "DS11") (pin "J1") (pinfunction "NC_J1") (pintype "passive"))
    )
    (net (code "134") (name "unconnected-(DS11-NC-PadJ9)") (class "Default")
      (node (ref "DS11") (pin "J9") (pinfunction "NC_J9") (pintype "passive"))
    )
    (net (code "135") (name "unconnected-(DS11-NC-PadL1)") (class "Default")
      (node (ref "DS11") (pin "L1") (pinfunction "NC_L1") (pintype "passive"))
    )
    (net (code "136") (name "unconnected-(DS11-NC-PadL9)") (class "Default")
      (node (ref "DS11") (pin "L9") (pinfunction "NC_L9") (pintype "passive"))
    )
    (net (code "137") (name "unconnected-(DS11-NC-PadM7)") (class "Default")
      (node (ref "DS11") (pin "M7") (pinfunction "NC_M7") (pintype "passive"))
    )
    (net (code "138") (name "unconnected-(DS12-NC-PadJ1)") (class "Default")
      (node (ref "DS12") (pin "J1") (pinfunction "NC_J1") (pintype "passive"))
    )
    (net (code "139") (name "unconnected-(DS12-NC-PadJ9)") (class "Default")
      (node (ref "DS12") (pin "J9") (pinfunction "NC_J9") (pintype "passive"))
    )
    (net (code "140") (name "unconnected-(DS12-NC-PadL1)") (class "Default")
      (node (ref "DS12") (pin "L1") (pinfunction "NC_L1") (pintype "passive"))
    )
    (net (code "141") (name "unconnected-(DS12-NC-PadL9)") (class "Default")
      (node (ref "DS12") (pin "L9") (pinfunction "NC_L9") (pintype "passive"))
    )
    (net (code "142") (name "unconnected-(DS12-NC-PadM7)") (class "Default")
      (node (ref "DS12") (pin "M7") (pinfunction "NC_M7") (pintype "passive"))
    )
  )
)
